# Peggy_Tracker.net
KiCad netlist of a schematic drawn in Altium Designer
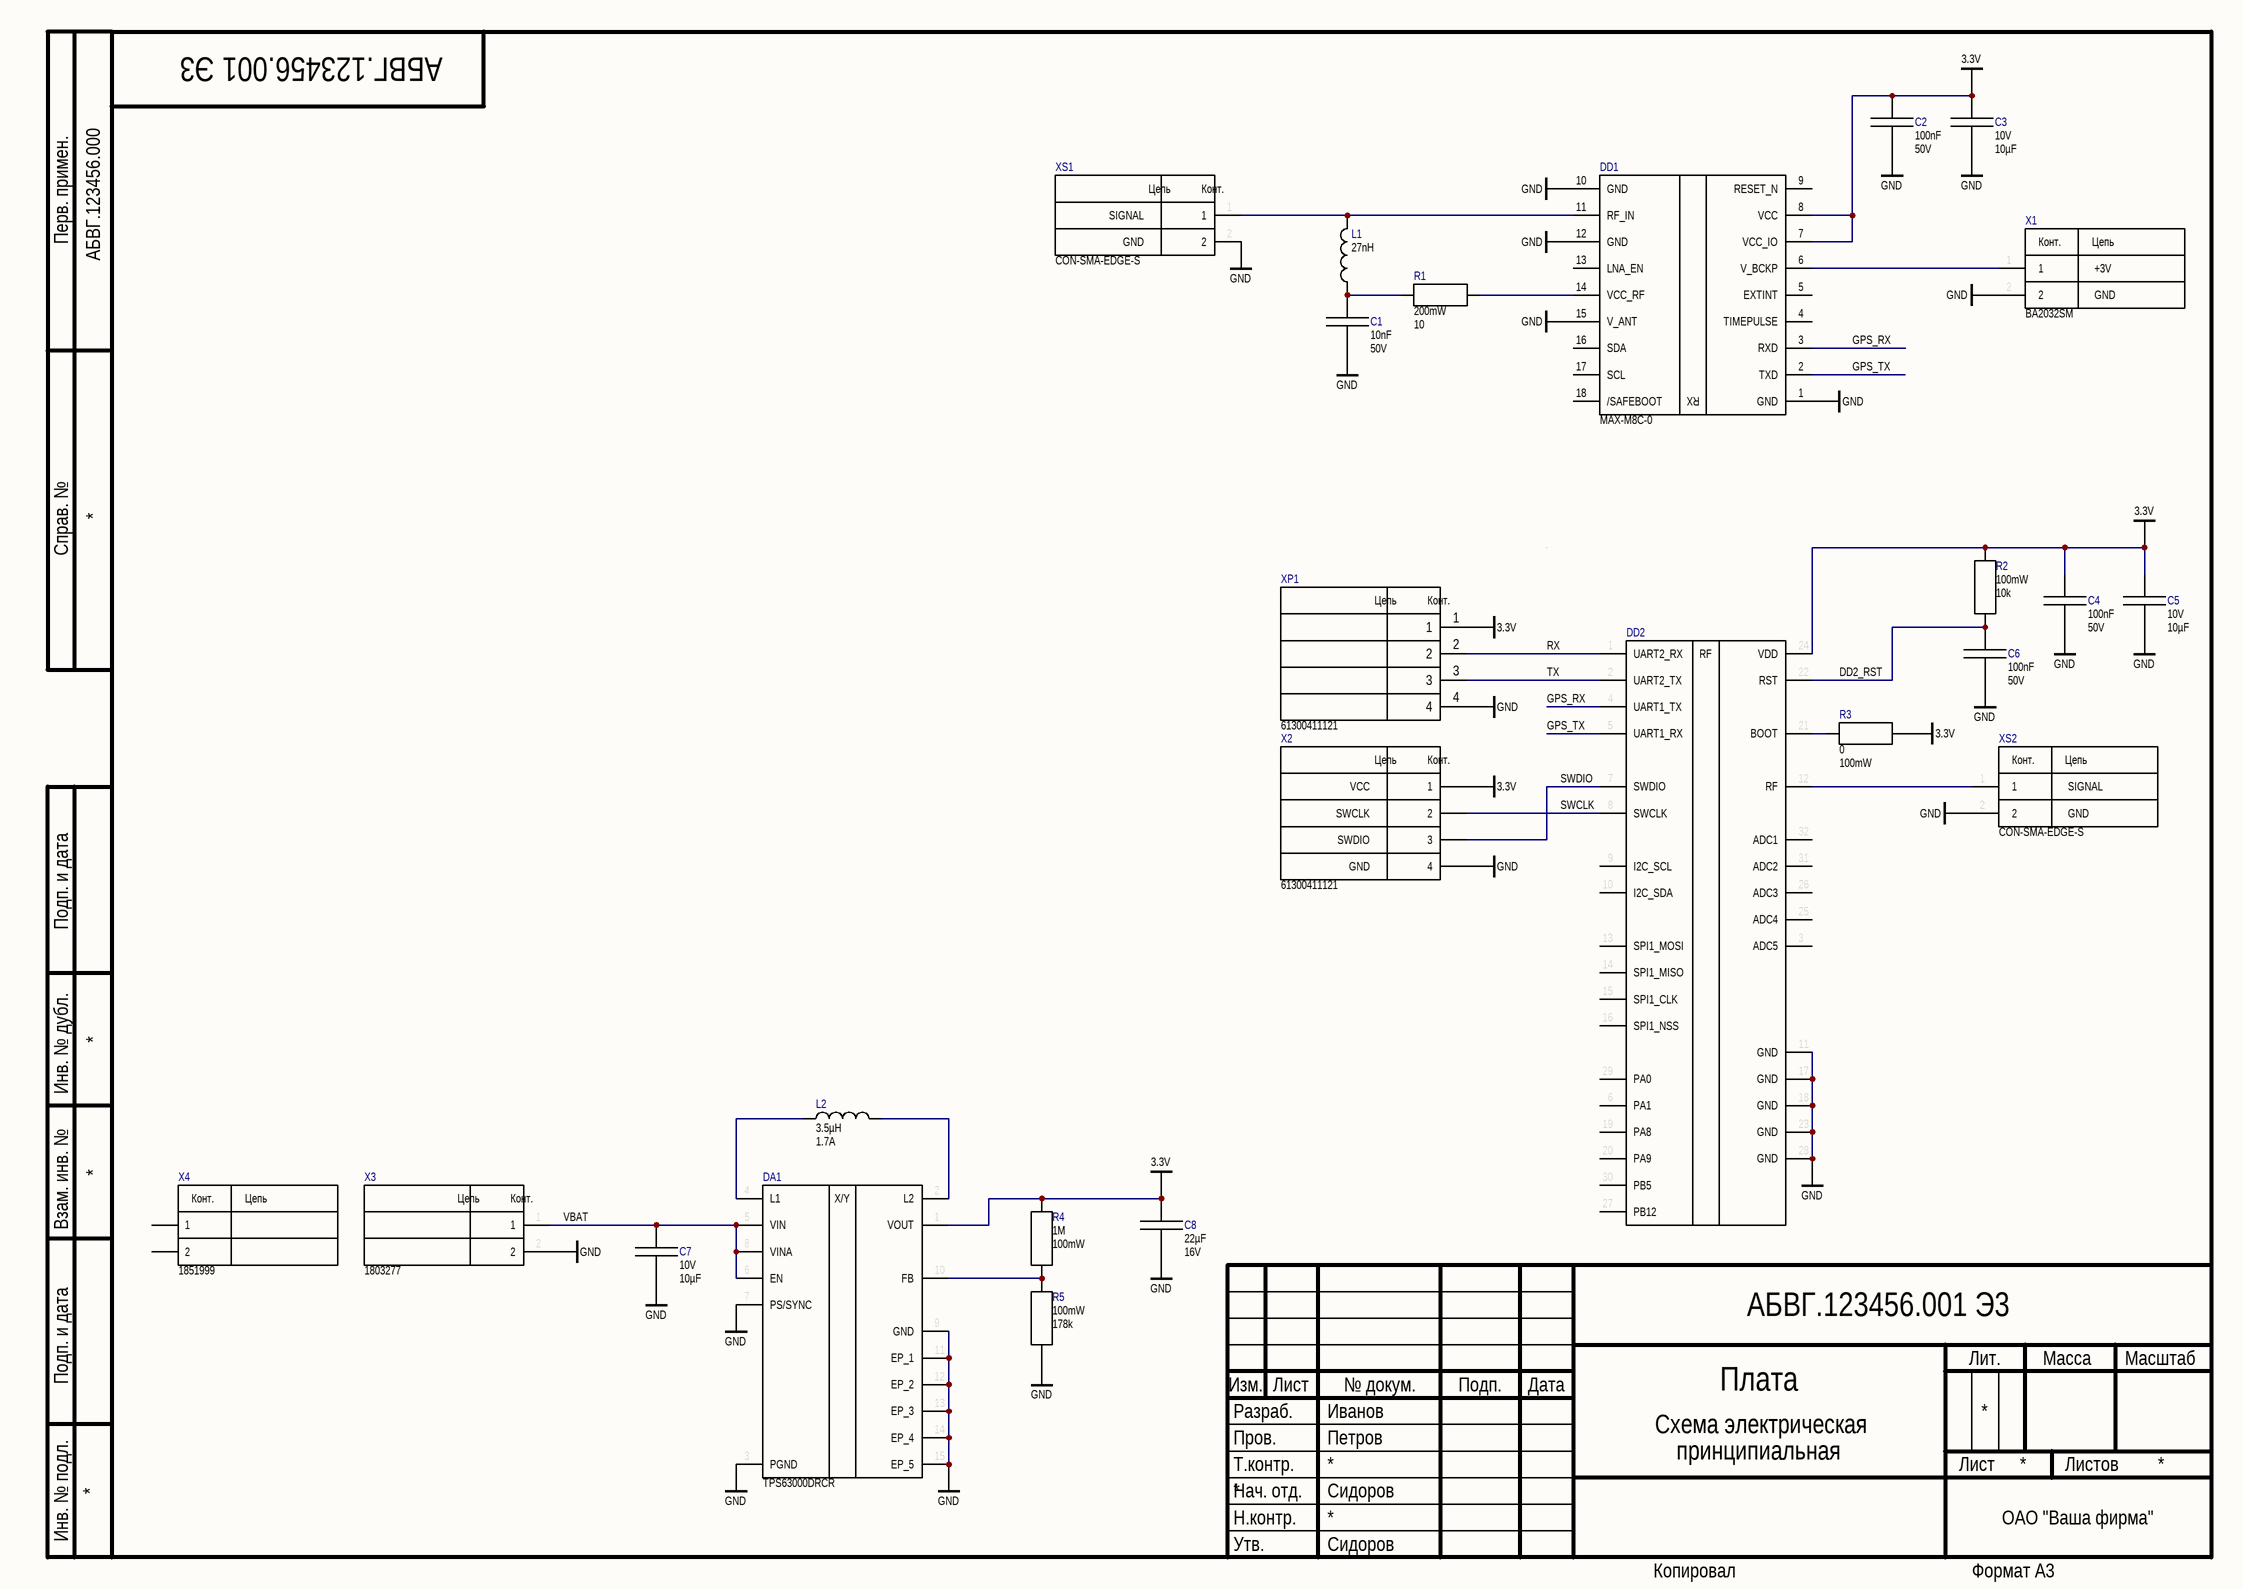
[diagram p0: Принципиальная схема Peggy Tracker.SchDoc]

(export (version "E")
  (design (tool "Eeschema 10.0.6"))
  (components
    (comp (ref "C1")
      (value "10nF")
      (footprint "CAPC1608X09N")
      (description "CAP CER 10000PF 50V X7R 0603")
      (fields
        (field (name "VOLTAGE") "50V")
        (field (name "MANUFACTURER") "Murata")
        (field (name "VOLTAGE RATING") "50V")
        (field (name "SOURCE") "Meteo_1.SCHLIB")
      )
      (libsource (lib "Sergek Concord Server") (part "CAP-NP-2"))
    )
    (comp (ref "C2")
      (value "100nF")
      (footprint "CAPC1608X09N")
      (description "CAP CER 0.1UF 50V X7R 0603")
      (fields
        (field (name "VOLTAGE RATING") "50V")
        (field (name "TOLERANCE") "10%")
        (field (name "MANUFACTURER PART NUMBER") "GCM188R71H104KA57D")
        (field (name "SOURCE") "Meteo_1.SCHLIB")
      )
      (libsource (lib "Sergek Concord Server") (part "CAP-NP-2"))
    )
    (comp (ref "C3")
      (value "CL21Y106KPQVPNE")
      (footprint "CAPC2013X135X45NL10T25")
      (description "CAP CER 10UF 10V X7S 0805")
      (fields
        (field (name "MANUFACTURER") "Samsung")
        (field (name "VOLTAGE RATING") "10V")
        (field (name "CAPACITANCE") "10µF")
        (field (name "TOLERANCE") "10%")
      )
      (libsource (lib "Sergek Concord Server") (part "CAP-NP-2"))
    )
    (comp (ref "C4")
      (value "100nF")
      (footprint "CAPC1608X09N")
      (description "CAP CER 0.1UF 50V X7R 0603")
      (fields
        (field (name "VOLTAGE RATING") "50V")
        (field (name "TOLERANCE") "10%")
        (field (name "MANUFACTURER PART NUMBER") "GCM188R71H104KA57D")
        (field (name "SOURCE") "Meteo_1.SCHLIB")
      )
      (libsource (lib "Sergek Concord Server") (part "CAP-NP-2"))
    )
    (comp (ref "C5")
      (value "CL21Y106KPQVPNE")
      (footprint "CAPC2013X135X45NL10T25")
      (description "CAP CER 10UF 10V X7S 0805")
      (fields
        (field (name "MANUFACTURER") "Samsung")
        (field (name "VOLTAGE RATING") "10V")
        (field (name "CAPACITANCE") "10µF")
        (field (name "TOLERANCE") "10%")
      )
      (libsource (lib "Sergek Concord Server") (part "CAP-NP-2"))
    )
    (comp (ref "C6")
      (value "100nF")
      (footprint "CAPC1608X09N")
      (description "CAP CER 0.1UF 50V X7R 0603")
      (fields
        (field (name "VOLTAGE RATING") "50V")
        (field (name "TOLERANCE") "10%")
        (field (name "MANUFACTURER PART NUMBER") "GCM188R71H104KA57D")
        (field (name "SOURCE") "Meteo_1.SCHLIB")
      )
      (libsource (lib "Sergek Concord Server") (part "CAP-NP-2"))
    )
    (comp (ref "C7")
      (value "CL21Y106KPQVPNE")
      (footprint "CAPC2013X135X45NL10T25")
      (description "CAP CER 10UF 10V X7S 0805")
      (fields
        (field (name "MANUFACTURER") "Samsung")
        (field (name "VOLTAGE RATING") "10V")
        (field (name "CAPACITANCE") "10µF")
        (field (name "TOLERANCE") "10%")
      )
      (libsource (lib "Sergek Concord Server") (part "CAP-NP-2"))
    )
    (comp (ref "C8")
      (value "22µF")
      (footprint "CAPC2013X140X45NL15T25")
      (fields
        (field (name "VOLTAGE RATING") "16V")
        (field (name "TOLERANCE") "10%")
        (field (name "MANUFACTURER PART NUMBER") "C2012X5R1C226K125AC")
        (field (name "MANUFACTURER") "TDK")
      )
      (libsource (lib "Sergek Concord Server") (part "CAP-NP-2"))
    )
    (comp (ref "DA1")
      (value "TPS63000IDRCRQ1")
      (footprint "TPS63002DRCR")
      (description "IC REG BUCK BOOST ADJ 1.6A 10SON")
      (fields
        (field (name "MANUFACTURER PART NUMBER") "TPS63000DRCR")
        (field (name "MANUFACTURER") "Texas Instruments")
      )
      (libsource (lib "Sergek Concord Server") (part "TPS63000"))
    )
    (comp (ref "DD1")
      (value "MAX-M8C-0")
      (footprint "MAXM8C0")
      (description "IC Receiver Gps/gnss 18LCC")
      (fields (field (name "MANUFACTURER") "u-blox") (field (name "MANUFACTURER PART NUMBER") "MAX-M8C-0"))
      (libsource (lib "Sergek Concord Server") (part "MAX-M8C-0"))
    )
    (comp (ref "DD2")
      (value "RAK3172(H)")
      (footprint "RAK3172(H)-Footprint-1")
      (description "RAK3172 WisDuo LPWAN Module")
      (fields (field (name "MANUFACTURER") "RAK Wireless"))
      (libsource (lib "Sergek Concord Server") (part "RAK3172(H)"))
    )
    (comp (ref "L1")
      (value "27nH")
      (footprint "INDC1005X55X25ML5T10")
      (description "INDUCTOR")
      (fields (field (name "TOLERANCE") "2%") (field (name "MANUFACTURER PART NUMBER") "LQW15AN27NG00D"))
      (libsource (lib "Sergek Concord Server") (part "IND-2"))
    )
    (comp (ref "L2")
      (value "3.5µH")
      (footprint "SRU5018680Y")
      (description "Ind Power Shielded Wirewound 3.5uH 30% 100KHz 9Q-Factor Ferrite 2.1A T/R")
      (fields
        (field (name "TOLERANCE") "30%")
        (field (name "SATURATION CURRENT") "1.7A")
        (field (name "MANUFACTURER") "Bourns")
      )
      (libsource (lib "Sergek Concord Server") (part "IND-2"))
    )
    (comp (ref "R1")
      (value "10")
      (footprint "RESC1608X95X40LL15T20")
      (description "Thick Film Resistors - SMD 0.2W 10ohm 5% 100ppm Anti-Pulse")
      (fields
        (field (name "TOLERANCE") "5%")
        (field (name "POWER RATING") "200mW")
        (field (name "Comment") "SG73P1JTTD100J")
      )
      (libsource (lib "") (part "RES-2_1"))
    )
    (comp (ref "R2")
      (value "RMCF0603FT10K0")
      (footprint "RESC1608X55X25LL10T15")
      (description "RES SMD 10K OHM 1% 1/10W 0603")
      (fields
        (field (name "MANUFACTURER") "Stackpole Electronics Inc")
        (field (name "POWER RATING") "100mW")
        (field (name "RESISTANCE") "10k")
        (field (name "TOLERANCE") "1%")
      )
      (libsource (lib "Sergek Concord Server") (part "RES-2"))
    )
    (comp (ref "R3")
      (value "0")
      (footprint "RESC1608X55X25LL10T15")
      (description "Res Thkflm 0603 0 Ohm Jumper 1/10W 100Ppm/ C Smd Rohs Compliant: Yes")
      (fields
        (field (name "MANUFACTURER") "Stackpole Electronics Inc")
        (field (name "POWER RATING") "100mW")
        (field (name "MANUFACTURER PART NUMBER") "RMCF0603ZT0R00")
      )
      (libsource (lib "") (part "RES-2_1"))
    )
    (comp (ref "R4")
      (value "1M")
      (footprint "RESC1608X95X40LL15T20")
      (description "RES 1M OHM 5% 1/10W 0603")
      (fields
        (field (name "POWER RATING") "100mW")
        (field (name "TOLERANCE") "5%")
        (field (name "MANUFACTURER PART NUMBER") "RMCF0603JT1M00")
      )
      (libsource (lib "Sergek Concord Server") (part "RES-2"))
    )
    (comp (ref "R5")
      (value "178k")
      (footprint "RESC1608X95X40LL15T20")
      (fields
        (field (name "TOLERANCE") "1%")
        (field (name "POWER RATING") "100mW")
        (field (name "MANUFACTURER PART NUMBER") "ERJ-3EKF1783V")
        (field (name "MANUFACTURER") "Panasonic")
      )
      (libsource (lib "Sergek Concord Server") (part "RES-2"))
    )
    (comp (ref "X1")
      (value "BA2032SM")
      (footprint "MPD-BA2032SM_V")
      (description "Battery Holder Coin 20MM SMD")
      (fields
        (field (name "MANUFACTURER") "Memory Protection Devices")
        (field (name "MANUFACTURER PART NUMBER") "BA2032SM")
      )
      (libsource (lib "Sergek Concord Server") (part "BATTERY-HOLDER-COIN-2"))
    )
    (comp (ref "X2")
      (value "ST-LINK-SWD-CONNECTOR")
      (footprint "20021311-00010T4LF-Footprint-1")
      (description "Conn Unshrouded Header HDR 4 POS 2.54mm Solder ST Thru-Hole Bag")
      (fields
        (field (name "MANUFACTURER PART NUMBER") "61300411121")
        (field (name "MANUFACTURER") "Würth Elektronik")
      )
      (libsource (lib "Sergek Concord Server") (part "ST-LINK-SWD"))
    )
    (comp (ref "X3")
      (value "1803277")
      (footprint "PHOE-1803277_V")
      (description "Male Header, Pitch 3.81 mm, 1 x 2 Position, Height 7.25 mm, Tail Length 3.4 mm, RoHS, Bulk")
      (fields
        (field (name "MANUFACTURER") "Phoenix Contact")
        (field (name "MANUFACTURER PART NUMBER") "1803277")
      )
      (libsource (lib "Sergek Concord Server") (part "CN-1P-M-R2"))
    )
    (comp (ref "X4")
      (value "1851999")
      (description "Pluggable Terminal Blocks 2 Pos 3.81mm pitch Plug 28-16 AWG Screw")
      (fields
        (field (name "MANUFACTURER PART NUMBER") "1851999")
        (field (name "VOLTAGE") "300V")
        (field (name "MANUFACTURER") "Phoenix Contact")
      )
      (libsource (lib "Sergek Concord Server") (part "X-2"))
    )
    (comp (ref "XP1")
      (value "61300411121")
      (footprint "20021311-00010T4LF-Footprint-1")
      (description "Conn Unshrouded Header HDR 4 POS 2.54mm Solder ST Thru-Hole Bag")
      (fields
        (field (name "MANUFACTURER") "Würth Elektronik")
        (field (name "MANUFACTURER PART NUMBER") "61300411121")
      )
      (libsource (lib "Sergek Concord Server") (part "XP-4"))
    )
    (comp (ref "XS1")
      (value "CON-SMA-EDGE-S")
      (footprint "RFSOLUTIONS_CON-SMA-EDGE-S")
      (description "CONN SMA JACK STR EDGE MNT")
      (fields
        (field (name "MANUFACTURER PART NUMBER") "CON-SMA-EDGE-S")
        (field (name "MANUFACTURER") "RF Solutions")
      )
      (libsource (lib "") (part "CON-SMA-EDGE-S_1"))
    )
    (comp (ref "XS2")
      (value "CON-SMA-EDGE-S")
      (footprint "RFSOLUTIONS_CON-SMA-EDGE-S")
      (description "CONN SMA JACK STR EDGE MNT")
      (fields
        (field (name "MANUFACTURER PART NUMBER") "CON-SMA-EDGE-S")
        (field (name "MANUFACTURER") "RF Solutions")
      )
      (libsource (lib "Sergek Concord Server") (part "CON-SMA-EDGE-S"))
    )
  )
  (nets
    (net (code "1") (name "/DD2_RST") (class "Default")
      (node (ref "C6") (pin "2") (pinfunction "2_2") (pintype "passive"))
      (node (ref "DD2") (pin "22") (pinfunction "RST_22") (pintype "passive"))
      (node (ref "R2") (pin "1") (pinfunction "1_1") (pintype "passive"))
    )
    (net (code "2") (name "/GPS_RX") (class "Default")
      (node (ref "DD1") (pin "3") (pinfunction "RXD_3") (pintype "passive"))
      (node (ref "DD2") (pin "4") (pinfunction "UART1_TX_4") (pintype "passive"))
    )
    (net (code "3") (name "/GPS_TX") (class "Default")
      (node (ref "DD1") (pin "2") (pinfunction "TXD_2") (pintype "passive"))
      (node (ref "DD2") (pin "5") (pinfunction "UART1_RX_5") (pintype "passive"))
    )
    (net (code "4") (name "/RX") (class "Default")
      (node (ref "DD2") (pin "1") (pinfunction "UART2_RX_1") (pintype "passive"))
      (node (ref "XP1") (pin "2") (pinfunction "2_2") (pintype "passive"))
    )
    (net (code "5") (name "/SWCLK") (class "Default")
      (node (ref "DD2") (pin "8") (pinfunction "SWCLK_8") (pintype "passive"))
      (node (ref "X2") (pin "2") (pinfunction "SWCLK_2") (pintype "passive"))
    )
    (net (code "6") (name "/SWDIO") (class "Default")
      (node (ref "DD2") (pin "7") (pinfunction "SWDIO_7") (pintype "passive"))
      (node (ref "X2") (pin "3") (pinfunction "SWDIO_3") (pintype "passive"))
    )
    (net (code "7") (name "/TX") (class "Default")
      (node (ref "DD2") (pin "2") (pinfunction "UART2_TX_2") (pintype "passive"))
      (node (ref "XP1") (pin "3") (pinfunction "3_3") (pintype "passive"))
    )
    (net (code "8") (name "/VBAT") (class "Default")
      (node (ref "C7") (pin "2") (pinfunction "2_2") (pintype "passive"))
      (node (ref "DA1") (pin "5") (pinfunction "VIN_5") (pintype "passive"))
      (node (ref "DA1") (pin "6") (pinfunction "EN_6") (pintype "passive"))
      (node (ref "DA1") (pin "8") (pinfunction "VINA_8") (pintype "passive"))
      (node (ref "X3") (pin "1") (pinfunction "1_1") (pintype "passive"))
    )
    (net (code "9") (name "3.3V") (class "Default")
      (node (ref "C2") (pin "1") (pinfunction "1_1") (pintype "passive"))
      (node (ref "C3") (pin "2") (pinfunction "2_2") (pintype "passive"))
      (node (ref "C4") (pin "2") (pinfunction "2_2") (pintype "passive"))
      (node (ref "C5") (pin "2") (pinfunction "2_2") (pintype "passive"))
      (node (ref "C8") (pin "2") (pinfunction "2_2") (pintype "passive"))
      (node (ref "DA1") (pin "1") (pinfunction "VOUT_1") (pintype "passive"))
      (node (ref "DD1") (pin "7") (pinfunction "VCC_IO_7") (pintype "passive"))
      (node (ref "DD1") (pin "8") (pinfunction "VCC_8") (pintype "passive"))
      (node (ref "DD2") (pin "24") (pinfunction "VDD_24") (pintype "passive"))
      (node (ref "R2") (pin "2") (pinfunction "2_2") (pintype "passive"))
      (node (ref "R3") (pin "2") (pinfunction "2_2") (pintype "passive"))
      (node (ref "R4") (pin "2") (pinfunction "2_2") (pintype "passive"))
      (node (ref "X2") (pin "1") (pinfunction "VCC_1") (pintype "passive"))
      (node (ref "XP1") (pin "1") (pinfunction "1_1") (pintype "passive"))
    )
    (net (code "10") (name "GND") (class "Default")
      (node (ref "C1") (pin "2") (pinfunction "2_2") (pintype "passive"))
      (node (ref "C2") (pin "2") (pinfunction "2_2") (pintype "passive"))
      (node (ref "C3") (pin "1") (pinfunction "1_1") (pintype "passive"))
      (node (ref "C4") (pin "1") (pinfunction "1_1") (pintype "passive"))
      (node (ref "C5") (pin "1") (pinfunction "1_1") (pintype "passive"))
      (node (ref "C6") (pin "1") (pinfunction "1_1") (pintype "passive"))
      (node (ref "C7") (pin "1") (pinfunction "1_1") (pintype "passive"))
      (node (ref "C8") (pin "1") (pinfunction "1_1") (pintype "passive"))
      (node (ref "DA1") (pin "11") (pinfunction "EP_1_11") (pintype "passive"))
      (node (ref "DA1") (pin "12") (pinfunction "EP_2_12") (pintype "passive"))
      (node (ref "DA1") (pin "13") (pinfunction "EP_3_13") (pintype "passive"))
      (node (ref "DA1") (pin "14") (pinfunction "EP_4_14") (pintype "passive"))
      (node (ref "DA1") (pin "15") (pinfunction "EP_5_15") (pintype "passive"))
      (node (ref "DA1") (pin "3") (pinfunction "PGND_3") (pintype "passive"))
      (node (ref "DA1") (pin "7") (pinfunction "PS/SYNC_7") (pintype "passive"))
      (node (ref "DA1") (pin "9") (pinfunction "GND_9") (pintype "passive"))
      (node (ref "DD1") (pin "1") (pinfunction "GND_1") (pintype "passive"))
      (node (ref "DD1") (pin "10") (pinfunction "GND_10") (pintype "passive"))
      (node (ref "DD1") (pin "12") (pinfunction "GND_12") (pintype "passive"))
      (node (ref "DD1") (pin "15") (pinfunction "V_ANT_15") (pintype "passive"))
      (node (ref "DD2") (pin "11") (pinfunction "GND_11") (pintype "passive"))
      (node (ref "DD2") (pin "17") (pinfunction "GND_17") (pintype "passive"))
      (node (ref "DD2") (pin "18") (pinfunction "GND_18") (pintype "passive"))
      (node (ref "DD2") (pin "23") (pinfunction "GND_23") (pintype "passive"))
      (node (ref "DD2") (pin "28") (pinfunction "GND_28") (pintype "passive"))
      (node (ref "R5") (pin "1") (pinfunction "1_1") (pintype "passive"))
      (node (ref "X1") (pin "2") (pinfunction "GND_2") (pintype "passive"))
      (node (ref "X2") (pin "4") (pinfunction "GND_4") (pintype "passive"))
      (node (ref "X3") (pin "2") (pinfunction "2_2") (pintype "passive"))
      (node (ref "XP1") (pin "4") (pinfunction "4_4") (pintype "passive"))
      (node (ref "XS1") (pin "2") (pinfunction "GND_2") (pintype "passive"))
      (node (ref "XS2") (pin "2") (pinfunction "GND_2") (pintype "passive"))
    )
    (net (code "11") (name "Net-(C1-Pad1)") (class "Default")
      (node (ref "C1") (pin "1") (pinfunction "1_1") (pintype "passive"))
      (node (ref "L1") (pin "1") (pinfunction "1_1") (pintype "passive"))
      (node (ref "R1") (pin "1") (pinfunction "1_1") (pintype "passive"))
    )
    (net (code "12") (name "Net-(DA1-FB)") (class "Default")
      (node (ref "DA1") (pin "10") (pinfunction "FB_10") (pintype "passive"))
      (node (ref "R4") (pin "1") (pinfunction "1_1") (pintype "passive"))
      (node (ref "R5") (pin "2") (pinfunction "2_2") (pintype "passive"))
    )
    (net (code "13") (name "Net-(DA1-L1)") (class "Default")
      (node (ref "DA1") (pin "4") (pinfunction "L1_4") (pintype "passive"))
      (node (ref "L2") (pin "1") (pinfunction "1_1") (pintype "passive"))
    )
    (net (code "14") (name "Net-(DA1-L2)") (class "Default")
      (node (ref "DA1") (pin "2") (pinfunction "L2_2") (pintype "passive"))
      (node (ref "L2") (pin "2") (pinfunction "2_2") (pintype "passive"))
    )
    (net (code "15") (name "Net-(DD1-RF_IN)") (class "Default")
      (node (ref "DD1") (pin "11") (pinfunction "RF_IN_11") (pintype "passive"))
      (node (ref "L1") (pin "2") (pinfunction "2_2") (pintype "passive"))
      (node (ref "XS1") (pin "1") (pinfunction "SIGNAL_1") (pintype "passive"))
    )
    (net (code "16") (name "Net-(DD1-VCC_RF)") (class "Default")
      (node (ref "DD1") (pin "14") (pinfunction "VCC_RF_14") (pintype "passive"))
      (node (ref "R1") (pin "2") (pinfunction "2_2") (pintype "passive"))
    )
    (net (code "17") (name "Net-(DD1-V_BCKP)") (class "Default")
      (node (ref "DD1") (pin "6") (pinfunction "V_BCKP_6") (pintype "passive"))
      (node (ref "X1") (pin "1") (pinfunction "+3V_1") (pintype "passive"))
    )
    (net (code "18") (name "Net-(DD2-BOOT)") (class "Default")
      (node (ref "DD2") (pin "21") (pinfunction "BOOT_21") (pintype "passive"))
      (node (ref "R3") (pin "1") (pinfunction "1_1") (pintype "passive"))
    )
    (net (code "19") (name "Net-(DD2-RF)") (class "Default")
      (node (ref "DD2") (pin "12") (pinfunction "RF_12") (pintype "passive"))
      (node (ref "XS2") (pin "1") (pinfunction "SIGNAL_1") (pintype "passive"))
    )
    (net (code "20") (name "unconnected-(DD1-EXTINT-Pad5)") (class "Default")
      (node (ref "DD1") (pin "5") (pinfunction "EXTINT_5") (pintype "passive"))
    )
    (net (code "21") (name "unconnected-(DD1-LNA_EN-Pad13)") (class "Default")
      (node (ref "DD1") (pin "13") (pinfunction "LNA_EN_13") (pintype "passive"))
    )
    (net (code "22") (name "unconnected-(DD1-RESET_N-Pad9)") (class "Default")
      (node (ref "DD1") (pin "9") (pinfunction "RESET_N_9") (pintype "passive"))
    )
    (net (code "23") (name "unconnected-(DD1-SCL-Pad17)") (class "Default")
      (node (ref "DD1") (pin "17") (pinfunction "SCL_17") (pintype "passive"))
    )
    (net (code "24") (name "unconnected-(DD1-SDA-Pad16)") (class "Default")
      (node (ref "DD1") (pin "16") (pinfunction "SDA_16") (pintype "passive"))
    )
    (net (code "25") (name "unconnected-(DD1-TIMEPULSE-Pad4)") (class "Default")
      (node (ref "DD1") (pin "4") (pinfunction "TIMEPULSE_4") (pintype "passive"))
    )
    (net (code "26") (name "unconnected-(DD1-{slash}SAFEBOOT-Pad18)") (class "Default")
      (node (ref "DD1") (pin "18") (pinfunction "/SAFEBOOT_18") (pintype "passive"))
    )
    (net (code "27") (name "unconnected-(DD2-ADC1-Pad32)") (class "Default")
      (node (ref "DD2") (pin "32") (pinfunction "ADC1_32") (pintype "passive"))
    )
    (net (code "28") (name "unconnected-(DD2-ADC2-Pad31)") (class "Default")
      (node (ref "DD2") (pin "31") (pinfunction "ADC2_31") (pintype "passive"))
    )
    (net (code "29") (name "unconnected-(DD2-ADC3-Pad26)") (class "Default")
      (node (ref "DD2") (pin "26") (pinfunction "ADC3_26") (pintype "passive"))
    )
    (net (code "30") (name "unconnected-(DD2-ADC4-Pad25)") (class "Default")
      (node (ref "DD2") (pin "25") (pinfunction "ADC4_25") (pintype "passive"))
    )
    (net (code "31") (name "unconnected-(DD2-ADC5-Pad3)") (class "Default")
      (node (ref "DD2") (pin "3") (pinfunction "ADC5_3") (pintype "passive"))
    )
    (net (code "32") (name "unconnected-(DD2-I2C_SCL-Pad9)") (class "Default")
      (node (ref "DD2") (pin "9") (pinfunction "I2C_SCL_9") (pintype "passive"))
    )
    (net (code "33") (name "unconnected-(DD2-I2C_SDA-Pad10)") (class "Default")
      (node (ref "DD2") (pin "10") (pinfunction "I2C_SDA_10") (pintype "passive"))
    )
    (net (code "34") (name "unconnected-(DD2-PA0-Pad29)") (class "Default")
      (node (ref "DD2") (pin "29") (pinfunction "PA0_29") (pintype "passive"))
    )
    (net (code "35") (name "unconnected-(DD2-PA1-Pad6)") (class "Default")
      (node (ref "DD2") (pin "6") (pinfunction "PA1_6") (pintype "passive"))
    )
    (net (code "36") (name "unconnected-(DD2-PA8-Pad19)") (class "Default")
      (node (ref "DD2") (pin "19") (pinfunction "PA8_19") (pintype "passive"))
    )
    (net (code "37") (name "unconnected-(DD2-PA9-Pad20)") (class "Default")
      (node (ref "DD2") (pin "20") (pinfunction "PA9_20") (pintype "passive"))
    )
    (net (code "38") (name "unconnected-(DD2-PB5-Pad30)") (class "Default")
      (node (ref "DD2") (pin "30") (pinfunction "PB5_30") (pintype "passive"))
    )
    (net (code "39") (name "unconnected-(DD2-PB12-Pad27)") (class "Default")
      (node (ref "DD2") (pin "27") (pinfunction "PB12_27") (pintype "passive"))
    )
    (net (code "40") (name "unconnected-(DD2-SPI1_CLK-Pad15)") (class "Default")
      (node (ref "DD2") (pin "15") (pinfunction "SPI1_CLK_15") (pintype "passive"))
    )
    (net (code "41") (name "unconnected-(DD2-SPI1_MISO-Pad14)") (class "Default")
      (node (ref "DD2") (pin "14") (pinfunction "SPI1_MISO_14") (pintype "passive"))
    )
    (net (code "42") (name "unconnected-(DD2-SPI1_MOSI-Pad13)") (class "Default")
      (node (ref "DD2") (pin "13") (pinfunction "SPI1_MOSI_13") (pintype "passive"))
    )
    (net (code "43") (name "unconnected-(DD2-SPI1_NSS-Pad16)") (class "Default")
      (node (ref "DD2") (pin "16") (pinfunction "SPI1_NSS_16") (pintype "passive"))
    )
    (net (code "44") (name "unconnected-(X4-Pad1)") (class "Default")
      (node (ref "X4") (pin "1") (pinfunction "1_1") (pintype "passive"))
    )
    (net (code "45") (name "unconnected-(X4-Pad2)") (class "Default")
      (node (ref "X4") (pin "2") (pinfunction "2_2") (pintype "passive"))
    )
  )
)
